# PLD_I2C-Repeater.net
KiCad netlist of a schematic drawn in Altium Designer
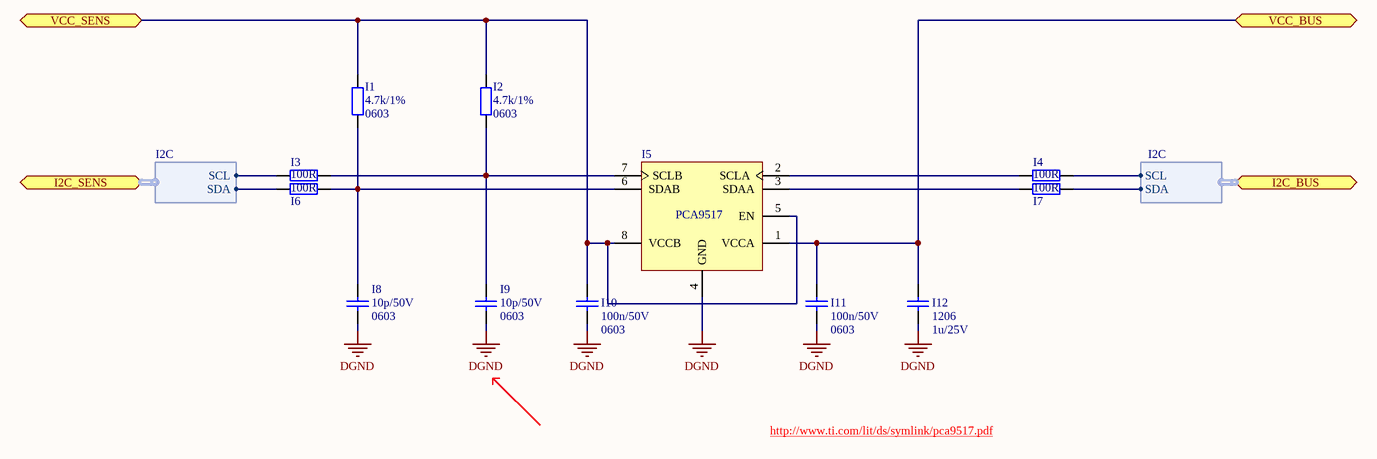
[diagram p0: PLD_I2C-Repeater.SchDoc]

(export (version "E")
  (design (tool "Eeschema 10.0.6"))
  (components
    (comp (ref "I1")
      (value "4.7k/1%")
      (footprint "SMD_Resistor_0603")
      (description "4.7k/1% Vishay CRCW 0603 Resistor. 100mW, 100ppm, 75V.")
      (fields
        (field (name "MANUFACTURER") "Vishay")
        (field (name "MANUFACTUERPARTNUMBER") "CRCW06034K70FKxxxx")
        (field (name "PACKAGE") "0603")
      )
      (libsource (lib "resistors") (part "CRCW06034K70FKxxxx"))
    )
    (comp (ref "I2")
      (value "4.7k/1%")
      (footprint "SMD_Resistor_0603")
      (description "4.7k/1% Vishay CRCW 0603 Resistor. 100mW, 100ppm, 75V.")
      (fields
        (field (name "MANUFACTURER") "Vishay")
        (field (name "MANUFACTUERPARTNUMBER") "CRCW06034K70FKxxxx")
        (field (name "PACKAGE") "0603")
      )
      (libsource (lib "resistors") (part "CRCW06034K70FKxxxx"))
    )
    (comp (ref "I3")
      (value "100R")
      (footprint "SMD_Resistor_0603")
      (libsource (lib "resistors") (part "Res"))
    )
    (comp (ref "I4")
      (value "100R")
      (footprint "SMD_Resistor_0603")
      (libsource (lib "resistors") (part "Res"))
    )
    (comp (ref "I5")
      (value "PCA9517")
      (footprint "TSSOP8_L")
      (description "Level-Translating I2C Bus Repeater")
      (fields
        (field (name "MANUFACTURER") "Texas Instruments")
        (field (name "MANUFACTURERPARTNUMBER") "PCA9517")
      )
      (libsource (lib "microcircuits") (part "PCA9517"))
    )
    (comp (ref "I6")
      (value "100R")
      (footprint "SMD_Resistor_0603")
      (libsource (lib "resistors") (part "Res"))
    )
    (comp (ref "I7")
      (value "100R")
      (footprint "SMD_Resistor_0603")
      (libsource (lib "resistors") (part "Res"))
    )
    (comp (ref "I8")
      (value "10p/50V")
      (footprint "SMD_Capacitor_0603")
      (description "Ceramic Cap Murata Automotive 10p/50V C0G 0603")
      (fields
        (field (name "MANUFACTURER") "Murata")
        (field (name "MANUFACTURERPARTNUMBER") "GCM1885C1H100JA16D")
        (field (name "PACKAGE") "0603")
      )
      (libsource (lib "capacitors") (part "Cer_GCM1885C1H100JA16D"))
    )
    (comp (ref "I9")
      (value "10p/50V")
      (footprint "SMD_Capacitor_0603")
      (description "Ceramic Cap Murata Automotive 10p/50V C0G 0603")
      (fields
        (field (name "MANUFACTURER") "Murata")
        (field (name "MANUFACTURERPARTNUMBER") "GCM1885C1H100JA16D")
        (field (name "PACKAGE") "0603")
      )
      (libsource (lib "capacitors") (part "Cer_GCM1885C1H100JA16D"))
    )
    (comp (ref "I10")
      (value "100n/50V")
      (footprint "SMD_Capacitor_0603")
      (description "Ceramic Cap Kemet COTS 100n/50V X7R 0603")
      (fields
        (field (name "MANUFACTURER") "Kemet")
        (field (name "MANUFACTURERPARTNUMBER") "C0603T104K5RALTU")
        (field (name "PACKAGE") "0603")
      )
      (libsource (lib "capacitors") (part "Cer_C0603T104K5RALTU"))
    )
    (comp (ref "I11")
      (value "100n/50V")
      (footprint "SMD_Capacitor_0603")
      (description "Ceramic Cap Kemet COTS 100n/50V X7R 0603")
      (fields
        (field (name "MANUFACTURER") "Kemet")
        (field (name "MANUFACTURERPARTNUMBER") "C0603T104K5RALTU")
        (field (name "PACKAGE") "0603")
      )
      (libsource (lib "capacitors") (part "Cer_C0603T104K5RALTU"))
    )
    (comp (ref "I12")
      (value "1u/25V")
      (footprint "SMD_Capacitor_1206")
      (description "Ceramic Cap Kemet COTS 1u/25V X7R 1206")
      (fields
        (field (name "MANUFACTURERPARTNUMBER") "C1206T105K3RALTU")
        (field (name "MANUFACTURER") "Kemet")
        (field (name "PACKAGE") "1206")
      )
      (libsource (lib "capacitors") (part "Cer_C1206T105K3RALTU"))
    )
  )
  (nets
    (net (code "2") (name "/VCC_BUS") (class "Default")
      (node (ref "I11") (pin "2") (pinfunction "2_2") (pintype "passive"))
      (node (ref "I12") (pin "2") (pinfunction "2_2") (pintype "passive"))
      (node (ref "I5") (pin "1") (pinfunction "VCCA_1") (pintype "passive"))
    )
    (net (code "3") (name "/VCC_SENS") (class "Default")
      (node (ref "I1") (pin "1") (pinfunction "1_1") (pintype "passive"))
      (node (ref "I10") (pin "2") (pinfunction "2_2") (pintype "passive"))
      (node (ref "I2") (pin "1") (pinfunction "1_1") (pintype "passive"))
      (node (ref "I5") (pin "5") (pinfunction "EN_5") (pintype "passive"))
      (node (ref "I5") (pin "8") (pinfunction "VCCB_8") (pintype "passive"))
    )
    (net (code "5") (name "DGND") (class "Default")
      (node (ref "I10") (pin "1") (pinfunction "1_1") (pintype "passive"))
      (node (ref "I11") (pin "1") (pinfunction "1_1") (pintype "passive"))
      (node (ref "I12") (pin "1") (pinfunction "1_1") (pintype "passive"))
      (node (ref "I5") (pin "4") (pinfunction "GND_4") (pintype "passive"))
      (node (ref "I8") (pin "2") (pinfunction "2_2") (pintype "passive"))
      (node (ref "I9") (pin "2") (pinfunction "2_2") (pintype "passive"))
    )
    (net (code "6") (name "Net-(I5-SCLA)") (class "Default")
      (node (ref "I4") (pin "1") (pinfunction "1_1") (pintype "passive"))
      (node (ref "I5") (pin "2") (pinfunction "SCLA_2") (pintype "passive"))
    )
    (net (code "7") (name "Net-(I5-SCLB)") (class "Default")
      (node (ref "I2") (pin "2") (pinfunction "2_2") (pintype "passive"))
      (node (ref "I3") (pin "2") (pinfunction "2_2") (pintype "passive"))
      (node (ref "I5") (pin "7") (pinfunction "SCLB_7") (pintype "passive"))
      (node (ref "I9") (pin "1") (pinfunction "1_1") (pintype "passive"))
    )
    (net (code "8") (name "Net-(I5-SDAA)") (class "Default")
      (node (ref "I5") (pin "3") (pinfunction "SDAA_3") (pintype "passive"))
      (node (ref "I7") (pin "1") (pinfunction "1_1") (pintype "passive"))
    )
    (net (code "9") (name "Net-(I5-SDAB)") (class "Default")
      (node (ref "I1") (pin "2") (pinfunction "2_2") (pintype "passive"))
      (node (ref "I5") (pin "6") (pinfunction "SDAB_6") (pintype "passive"))
      (node (ref "I6") (pin "2") (pinfunction "2_2") (pintype "passive"))
      (node (ref "I8") (pin "1") (pinfunction "1_1") (pintype "passive"))
    )
    (net (code "10") (name "unconnected-(I3-Pad1)") (class "Default")
      (node (ref "I3") (pin "1") (pinfunction "1_1") (pintype "passive"))
    )
    (net (code "11") (name "unconnected-(I4-Pad2)") (class "Default")
      (node (ref "I4") (pin "2") (pinfunction "2_2") (pintype "passive"))
    )
    (net (code "12") (name "unconnected-(I6-Pad1)") (class "Default")
      (node (ref "I6") (pin "1") (pinfunction "1_1") (pintype "passive"))
    )
    (net (code "13") (name "unconnected-(I7-Pad2)") (class "Default")
      (node (ref "I7") (pin "2") (pinfunction "2_2") (pintype "passive"))
    )
  )
)
